# Jetson_PCB.net
KiCad netlist of a schematic drawn in Altium Designer
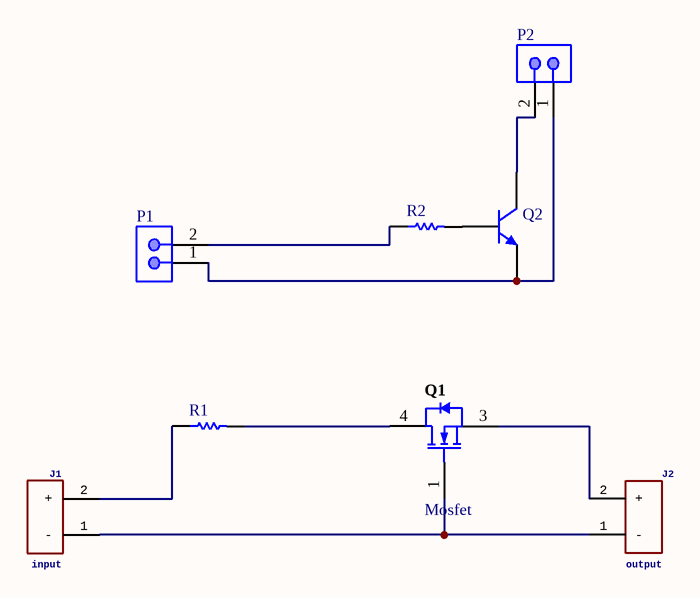
[diagram p0: Jetson_PCB.SchDoc]

(export (version "E")
  (design (tool "Eeschema 10.0.6"))
  (components
    (comp (ref "J1")
      (value "input")
      (footprint "AMASS_XT60-M")
      (fields (field (name "MF") "AMASS") (field (name "MP") "XT60-M"))
      (libsource (lib "XT60-M") (part "XT60-M"))
    )
    (comp (ref "J2")
      (value "output")
      (footprint "AMASS_XT60-M")
      (fields (field (name "MF") "AMASS") (field (name "MP") "XT60-M"))
      (libsource (lib "XT60-M") (part "XT60-M"))
    )
    (comp (ref "P1")
      (value "B2B-EH-A")
      (footprint "JST-B2B-EH-A_V")
      (fields (field (name "MANUFACTURER") "JST"))
      (libsource (lib "Altium Content Vault") (part "CN-1P-M-R2"))
    )
    (comp (ref "P2")
      (value "B2B-EH-A")
      (footprint "JST-B2B-EH-A_V")
      (fields (field (name "MANUFACTURER") "JST"))
      (libsource (lib "") (part "CN-1P-M-R2_1"))
    )
    (comp (ref "Q1")
      (value "Mosfet")
      (footprint "FAIR-TO-252-3_V")
      (fields (field (name "MANUFACTURER") "FairchildSemiconductor"))
      (libsource (lib "Altium Content Vault") (part "NEMOS-GSD-3_C"))
    )
    (comp (ref "Q2")
      (value "2N3904")
      (footprint "TO-92A")
      (description "NPN General Purpose Amplifier")
      (fields (field (name "PUBLISHER") "Altium Limited"))
      (libsource (lib "Miscellaneous Devices") (part "2N3904"))
    )
    (comp (ref "R1")
      (value "RR1220P-561-D")
      (footprint "RESC2013X50X40ML20T20")
      (fields (field (name "MANUFACTURER") "Susumu"))
      (libsource (lib "Altium Content Vault") (part "RES"))
    )
    (comp (ref "R2")
      (value "RR1220P-561-D")
      (footprint "RESC2013X50X40ML20T20")
      (fields (field (name "MANUFACTURER") "Susumu"))
      (libsource (lib "Altium Content Vault") (part "RES"))
    )
  )
  (nets
    (net (code "1") (name "Net-(J1-+)") (class "Default")
      (node (ref "J1") (pin "2") (pinfunction "+_2") (pintype "passive"))
      (node (ref "R1") (pin "1") (pinfunction "1_1") (pintype "passive"))
    )
    (net (code "2") (name "Net-(J1--)") (class "Default")
      (node (ref "J1") (pin "1") (pinfunction "-_1") (pintype "passive"))
      (node (ref "J2") (pin "1") (pinfunction "-_1") (pintype "passive"))
      (node (ref "Q1") (pin "1") (pinfunction "G_1") (pintype "passive"))
    )
    (net (code "3") (name "Net-(J2-+)") (class "Default")
      (node (ref "J2") (pin "2") (pinfunction "+_2") (pintype "passive"))
      (node (ref "Q1") (pin "3") (pinfunction "S_3") (pintype "passive"))
    )
    (net (code "4") (name "Net-(P1-Pad2)") (class "Default")
      (node (ref "P1") (pin "2") (pinfunction "2_2") (pintype "passive"))
      (node (ref "R2") (pin "1") (pinfunction "1_1") (pintype "passive"))
    )
    (net (code "5") (name "Net-(Q1-D)") (class "Default")
      (node (ref "Q1") (pin "4") (pinfunction "D_4") (pintype "passive"))
      (node (ref "R1") (pin "2") (pinfunction "2_2") (pintype "passive"))
    )
    (net (code "6") (name "Net-(Q2-B)") (class "Default")
      (node (ref "Q2") (pin "2") (pinfunction "B_2") (pintype "passive"))
      (node (ref "R2") (pin "2") (pinfunction "2_2") (pintype "passive"))
    )
    (net (code "7") (name "Net-(Q2-C)") (class "Default")
      (node (ref "P2") (pin "2") (pinfunction "2_2") (pintype "passive"))
      (node (ref "Q2") (pin "3") (pinfunction "C_3") (pintype "passive"))
    )
    (net (code "8") (name "Net-(Q2-E)") (class "Default")
      (node (ref "P1") (pin "1") (pinfunction "1_1") (pintype "passive"))
      (node (ref "P2") (pin "1") (pinfunction "1_1") (pintype "passive"))
      (node (ref "Q2") (pin "1") (pinfunction "E_1") (pintype "passive"))
    )
  )
)
